# Board.net
KiCad netlist of a schematic drawn in EAGLE
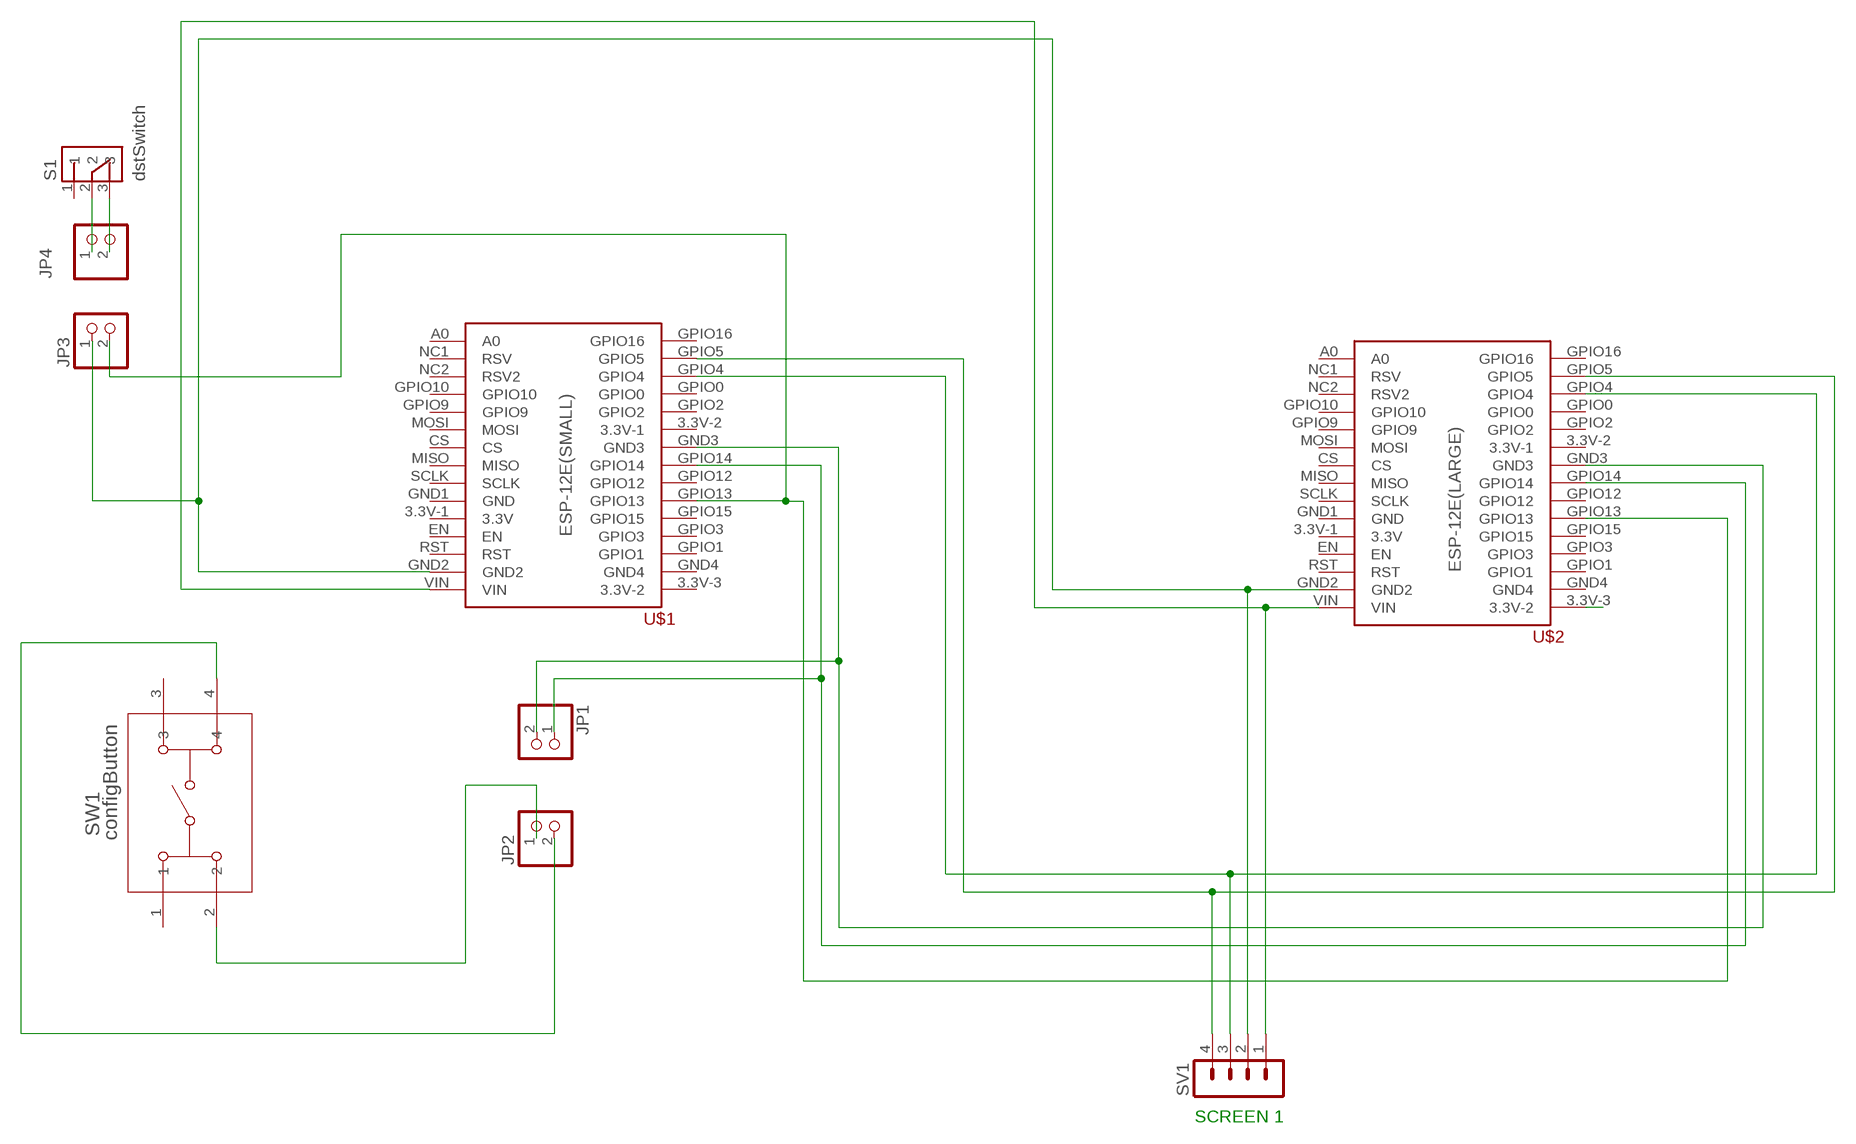
[diagram p0: schematic, sheet 1]

(export (version "E")
  (design (tool "Eeschema 10.0.6"))
  (components
    (comp (ref "JP1")
      (value "PINHD-1X2/90")
      (footprint "eagle-import:1X02_90")
      (libsource (lib "eagle-import") (part "PINHD-1X2/90"))
    )
    (comp (ref "JP2")
      (value "PINHD-1X2/90")
      (footprint "eagle-import:1X02_90")
      (libsource (lib "eagle-import") (part "PINHD-1X2/90"))
    )
    (comp (ref "JP3")
      (value "PINHD-1X2/90")
      (footprint "eagle-import:1X02_90")
      (libsource (lib "eagle-import") (part "PINHD-1X2/90"))
    )
    (comp (ref "JP4")
      (value "PINHD-1X2/90")
      (footprint "eagle-import:1X02_90")
      (libsource (lib "eagle-import") (part "PINHD-1X2/90"))
    )
    (comp (ref "S1")
      (value "dstSwitch")
      (footprint "eagle-import:SW_OS102011MS2QN1")
      (fields
        (field (name "DIGI-KEY_PART_NUMBER") "CKN12284-ND")
        (field (name "MF") "C&K")
        (field (name "MP") "OS102011MS2QN1")
      )
      (libsource (lib "eagle-import") (part "OS102011MS2QN1"))
    )
    (comp (ref "SV1")
      (value "MA04-1")
      (footprint "eagle-import:MA04-1")
      (libsource (lib "eagle-import") (part "MA04-1"))
    )
    (comp (ref "SW1")
      (value "configButton")
      (footprint "eagle-import:SW4_1825910-B_TEC")
      (fields
        (field (name "MANUFACTURER_PART_NUMBER") "1825910-6")
        (field (name "COPYRIGHT") "Copyright (C) 2016 Accelerated Designs. All rights reserved")
      )
      (libsource (lib "eagle-import") (part "1825910-6"))
    )
    (comp (ref "U$1")
      (value "ESP-12F(SMALL)")
      (footprint "eagle-import:ESP-12E(SMALL)")
      (libsource (lib "eagle-import") (part "ESP-12F(SMALL)"))
    )
    (comp (ref "U$2")
      (value "ESP-12F(LARGE)")
      (footprint "eagle-import:ESP-12E(LARGE)")
      (libsource (lib "eagle-import") (part "ESP-12F(LARGE)"))
    )
  )
  (nets
    (net (code "1") (name "Net-(JP1-Pad1)") (class "Default")
      (node (ref "JP1") (pin "1") (pinfunction "1_1") (pintype "passive"))
      (node (ref "U$1") (pin "GPIO14") (pinfunction "GPIO14_GPIO14") (pintype "bidirectional"))
      (node (ref "U$2") (pin "GPIO14") (pinfunction "GPIO14_GPIO14") (pintype "bidirectional"))
    )
    (net (code "2") (name "Net-(JP1-Pad2)") (class "Default")
      (node (ref "JP1") (pin "2") (pinfunction "2_2") (pintype "passive"))
      (node (ref "U$1") (pin "GND3") (pinfunction "GND3_GND3") (pintype "bidirectional"))
      (node (ref "U$2") (pin "GND3") (pinfunction "GND3_GND3") (pintype "bidirectional"))
    )
    (net (code "3") (name "Net-(JP2-Pad1)") (class "Default")
      (node (ref "JP2") (pin "1") (pinfunction "1_1") (pintype "passive"))
      (node (ref "SW1") (pin "2") (pinfunction "2_2") (pintype "passive"))
    )
    (net (code "4") (name "Net-(JP2-Pad2)") (class "Default")
      (node (ref "JP2") (pin "2") (pinfunction "2_2") (pintype "passive"))
      (node (ref "SW1") (pin "4") (pinfunction "4_4") (pintype "passive"))
    )
    (net (code "5") (name "Net-(JP3-Pad1)") (class "Default")
      (node (ref "JP3") (pin "1") (pinfunction "1_1") (pintype "passive"))
      (node (ref "SV1") (pin "2") (pinfunction "2_2") (pintype "passive"))
      (node (ref "U$1") (pin "GND2") (pinfunction "GND2_GND2") (pintype "bidirectional"))
      (node (ref "U$2") (pin "GND2") (pinfunction "GND2_GND2") (pintype "bidirectional"))
    )
    (net (code "6") (name "Net-(JP3-Pad2)") (class "Default")
      (node (ref "JP3") (pin "2") (pinfunction "2_2") (pintype "passive"))
      (node (ref "U$1") (pin "GPIO13") (pinfunction "GPIO13_GPIO13") (pintype "bidirectional"))
      (node (ref "U$2") (pin "GPIO13") (pinfunction "GPIO13_GPIO13") (pintype "bidirectional"))
    )
    (net (code "7") (name "Net-(JP4-Pad1)") (class "Default")
      (node (ref "JP4") (pin "1") (pinfunction "1_1") (pintype "passive"))
      (node (ref "S1") (pin "2") (pinfunction "2_2") (pintype "passive"))
    )
    (net (code "8") (name "Net-(JP4-Pad2)") (class "Default")
      (node (ref "JP4") (pin "2") (pinfunction "2_2") (pintype "passive"))
      (node (ref "S1") (pin "3") (pinfunction "3_3") (pintype "passive"))
    )
    (net (code "9") (name "Net-(SV1-Pad1)") (class "Default")
      (node (ref "SV1") (pin "1") (pinfunction "1_1") (pintype "passive"))
      (node (ref "U$1") (pin "VIN") (pinfunction "VIN_VIN") (pintype "bidirectional"))
      (node (ref "U$2") (pin "VIN") (pinfunction "VIN_VIN") (pintype "bidirectional"))
    )
    (net (code "10") (name "Net-(SV1-Pad3)") (class "Default")
      (node (ref "SV1") (pin "3") (pinfunction "3_3") (pintype "passive"))
      (node (ref "U$1") (pin "GPIO4") (pinfunction "GPIO4_GPIO4") (pintype "bidirectional"))
      (node (ref "U$2") (pin "GPIO4") (pinfunction "GPIO4_GPIO4") (pintype "bidirectional"))
    )
    (net (code "11") (name "Net-(SV1-Pad4)") (class "Default")
      (node (ref "SV1") (pin "4") (pinfunction "4_4") (pintype "passive"))
      (node (ref "U$1") (pin "GPIO5") (pinfunction "GPIO5_GPIO5") (pintype "bidirectional"))
      (node (ref "U$2") (pin "GPIO5") (pinfunction "GPIO5_GPIO5") (pintype "bidirectional"))
    )
    (net (code "12") (name "unconnected-(S1-Pad1)") (class "Default")
      (node (ref "S1") (pin "1") (pinfunction "1_1") (pintype "passive"))
    )
    (net (code "13") (name "unconnected-(SW1-Pad1)") (class "Default")
      (node (ref "SW1") (pin "1") (pinfunction "1_1") (pintype "passive"))
    )
    (net (code "14") (name "unconnected-(SW1-Pad3)") (class "Default")
      (node (ref "SW1") (pin "3") (pinfunction "3_3") (pintype "passive"))
    )
    (net (code "15") (name "unconnected-(U$1-3.3V-1-Pad3.3V-2)") (class "Default")
      (node (ref "U$1") (pin "3.3V-2") (pinfunction "3.3V-1_3.3V-2") (pintype "bidirectional"))
    )
    (net (code "16") (name "unconnected-(U$1-3.3V-2-Pad3.3V-3)") (class "Default")
      (node (ref "U$1") (pin "3.3V-3") (pinfunction "3.3V-2_3.3V-3") (pintype "bidirectional"))
    )
    (net (code "17") (name "unconnected-(U$1-3.3V-Pad3.3V-1)") (class "Default")
      (node (ref "U$1") (pin "3.3V-1") (pinfunction "3.3V_3.3V-1") (pintype "bidirectional"))
    )
    (net (code "18") (name "unconnected-(U$1-GND-PadGND1)") (class "Default")
      (node (ref "U$1") (pin "GND1") (pinfunction "GND_GND1") (pintype "bidirectional"))
    )
    (net (code "19") (name "unconnected-(U$1-PadA0)") (class "Default")
      (node (ref "U$1") (pin "A0") (pinfunction "A0_A0") (pintype "bidirectional"))
    )
    (net (code "20") (name "unconnected-(U$1-PadCS)") (class "Default")
      (node (ref "U$1") (pin "CS") (pinfunction "CS_CS") (pintype "bidirectional"))
    )
    (net (code "21") (name "unconnected-(U$1-PadEN)") (class "Default")
      (node (ref "U$1") (pin "EN") (pinfunction "EN_EN") (pintype "bidirectional"))
    )
    (net (code "22") (name "unconnected-(U$1-PadGND4)") (class "Default")
      (node (ref "U$1") (pin "GND4") (pinfunction "GND4_GND4") (pintype "bidirectional"))
    )
    (net (code "23") (name "unconnected-(U$1-PadGPIO0)") (class "Default")
      (node (ref "U$1") (pin "GPIO0") (pinfunction "GPIO0_GPIO0") (pintype "bidirectional"))
    )
    (net (code "24") (name "unconnected-(U$1-PadGPIO1)") (class "Default")
      (node (ref "U$1") (pin "GPIO1") (pinfunction "GPIO1_GPIO1") (pintype "bidirectional"))
    )
    (net (code "25") (name "unconnected-(U$1-PadGPIO2)") (class "Default")
      (node (ref "U$1") (pin "GPIO2") (pinfunction "GPIO2_GPIO2") (pintype "bidirectional"))
    )
    (net (code "26") (name "unconnected-(U$1-PadGPIO3)") (class "Default")
      (node (ref "U$1") (pin "GPIO3") (pinfunction "GPIO3_GPIO3") (pintype "bidirectional"))
    )
    (net (code "27") (name "unconnected-(U$1-PadGPIO9)") (class "Default")
      (node (ref "U$1") (pin "GPIO9") (pinfunction "GPIO9_GPIO9") (pintype "bidirectional"))
    )
    (net (code "28") (name "unconnected-(U$1-PadGPIO10)") (class "Default")
      (node (ref "U$1") (pin "GPIO10") (pinfunction "GPIO10_GPIO10") (pintype "bidirectional"))
    )
    (net (code "29") (name "unconnected-(U$1-PadGPIO12)") (class "Default")
      (node (ref "U$1") (pin "GPIO12") (pinfunction "GPIO12_GPIO12") (pintype "bidirectional"))
    )
    (net (code "30") (name "unconnected-(U$1-PadGPIO15)") (class "Default")
      (node (ref "U$1") (pin "GPIO15") (pinfunction "GPIO15_GPIO15") (pintype "bidirectional"))
    )
    (net (code "31") (name "unconnected-(U$1-PadGPIO16)") (class "Default")
      (node (ref "U$1") (pin "GPIO16") (pinfunction "GPIO16_GPIO16") (pintype "bidirectional"))
    )
    (net (code "32") (name "unconnected-(U$1-PadMISO)") (class "Default")
      (node (ref "U$1") (pin "MISO") (pinfunction "MISO_MISO") (pintype "bidirectional"))
    )
    (net (code "33") (name "unconnected-(U$1-PadMOSI)") (class "Default")
      (node (ref "U$1") (pin "MOSI") (pinfunction "MOSI_MOSI") (pintype "bidirectional"))
    )
    (net (code "34") (name "unconnected-(U$1-PadRST)") (class "Default")
      (node (ref "U$1") (pin "RST") (pinfunction "RST_RST") (pintype "bidirectional"))
    )
    (net (code "35") (name "unconnected-(U$1-PadSCLK)") (class "Default")
      (node (ref "U$1") (pin "SCLK") (pinfunction "SCLK_SCLK") (pintype "bidirectional"))
    )
    (net (code "36") (name "unconnected-(U$1-RSV-PadNC1)") (class "Default")
      (node (ref "U$1") (pin "NC1") (pinfunction "RSV_NC1") (pintype "bidirectional"))
    )
    (net (code "37") (name "unconnected-(U$1-RSV2-PadNC2)") (class "Default")
      (node (ref "U$1") (pin "NC2") (pinfunction "RSV2_NC2") (pintype "bidirectional"))
    )
    (net (code "38") (name "unconnected-(U$2-3.3V-1-Pad3.3V-2)") (class "Default")
      (node (ref "U$2") (pin "3.3V-2") (pinfunction "3.3V-1_3.3V-2") (pintype "bidirectional"))
    )
    (net (code "39") (name "unconnected-(U$2-3.3V-2-Pad3.3V-3)") (class "Default")
      (node (ref "U$2") (pin "3.3V-3") (pinfunction "3.3V-2_3.3V-3") (pintype "bidirectional"))
    )
    (net (code "40") (name "unconnected-(U$2-3.3V-Pad3.3V-1)") (class "Default")
      (node (ref "U$2") (pin "3.3V-1") (pinfunction "3.3V_3.3V-1") (pintype "bidirectional"))
    )
    (net (code "41") (name "unconnected-(U$2-GND-PadGND1)") (class "Default")
      (node (ref "U$2") (pin "GND1") (pinfunction "GND_GND1") (pintype "bidirectional"))
    )
    (net (code "42") (name "unconnected-(U$2-PadA0)") (class "Default")
      (node (ref "U$2") (pin "A0") (pinfunction "A0_A0") (pintype "bidirectional"))
    )
    (net (code "43") (name "unconnected-(U$2-PadCS)") (class "Default")
      (node (ref "U$2") (pin "CS") (pinfunction "CS_CS") (pintype "bidirectional"))
    )
    (net (code "44") (name "unconnected-(U$2-PadEN)") (class "Default")
      (node (ref "U$2") (pin "EN") (pinfunction "EN_EN") (pintype "bidirectional"))
    )
    (net (code "45") (name "unconnected-(U$2-PadGND4)") (class "Default")
      (node (ref "U$2") (pin "GND4") (pinfunction "GND4_GND4") (pintype "bidirectional"))
    )
    (net (code "46") (name "unconnected-(U$2-PadGPIO0)") (class "Default")
      (node (ref "U$2") (pin "GPIO0") (pinfunction "GPIO0_GPIO0") (pintype "bidirectional"))
    )
    (net (code "47") (name "unconnected-(U$2-PadGPIO1)") (class "Default")
      (node (ref "U$2") (pin "GPIO1") (pinfunction "GPIO1_GPIO1") (pintype "bidirectional"))
    )
    (net (code "48") (name "unconnected-(U$2-PadGPIO2)") (class "Default")
      (node (ref "U$2") (pin "GPIO2") (pinfunction "GPIO2_GPIO2") (pintype "bidirectional"))
    )
    (net (code "49") (name "unconnected-(U$2-PadGPIO3)") (class "Default")
      (node (ref "U$2") (pin "GPIO3") (pinfunction "GPIO3_GPIO3") (pintype "bidirectional"))
    )
    (net (code "50") (name "unconnected-(U$2-PadGPIO9)") (class "Default")
      (node (ref "U$2") (pin "GPIO9") (pinfunction "GPIO9_GPIO9") (pintype "bidirectional"))
    )
    (net (code "51") (name "unconnected-(U$2-PadGPIO10)") (class "Default")
      (node (ref "U$2") (pin "GPIO10") (pinfunction "GPIO10_GPIO10") (pintype "bidirectional"))
    )
    (net (code "52") (name "unconnected-(U$2-PadGPIO12)") (class "Default")
      (node (ref "U$2") (pin "GPIO12") (pinfunction "GPIO12_GPIO12") (pintype "bidirectional"))
    )
    (net (code "53") (name "unconnected-(U$2-PadGPIO15)") (class "Default")
      (node (ref "U$2") (pin "GPIO15") (pinfunction "GPIO15_GPIO15") (pintype "bidirectional"))
    )
    (net (code "54") (name "unconnected-(U$2-PadGPIO16)") (class "Default")
      (node (ref "U$2") (pin "GPIO16") (pinfunction "GPIO16_GPIO16") (pintype "bidirectional"))
    )
    (net (code "55") (name "unconnected-(U$2-PadMISO)") (class "Default")
      (node (ref "U$2") (pin "MISO") (pinfunction "MISO_MISO") (pintype "bidirectional"))
    )
    (net (code "56") (name "unconnected-(U$2-PadMOSI)") (class "Default")
      (node (ref "U$2") (pin "MOSI") (pinfunction "MOSI_MOSI") (pintype "bidirectional"))
    )
    (net (code "57") (name "unconnected-(U$2-PadRST)") (class "Default")
      (node (ref "U$2") (pin "RST") (pinfunction "RST_RST") (pintype "bidirectional"))
    )
    (net (code "58") (name "unconnected-(U$2-PadSCLK)") (class "Default")
      (node (ref "U$2") (pin "SCLK") (pinfunction "SCLK_SCLK") (pintype "bidirectional"))
    )
    (net (code "59") (name "unconnected-(U$2-RSV-PadNC1)") (class "Default")
      (node (ref "U$2") (pin "NC1") (pinfunction "RSV_NC1") (pintype "bidirectional"))
    )
    (net (code "60") (name "unconnected-(U$2-RSV2-PadNC2)") (class "Default")
      (node (ref "U$2") (pin "NC2") (pinfunction "RSV2_NC2") (pintype "bidirectional"))
    )
  )
)
